# M_D_ext_power2.net
KiCad netlist of a schematic drawn in EAGLE
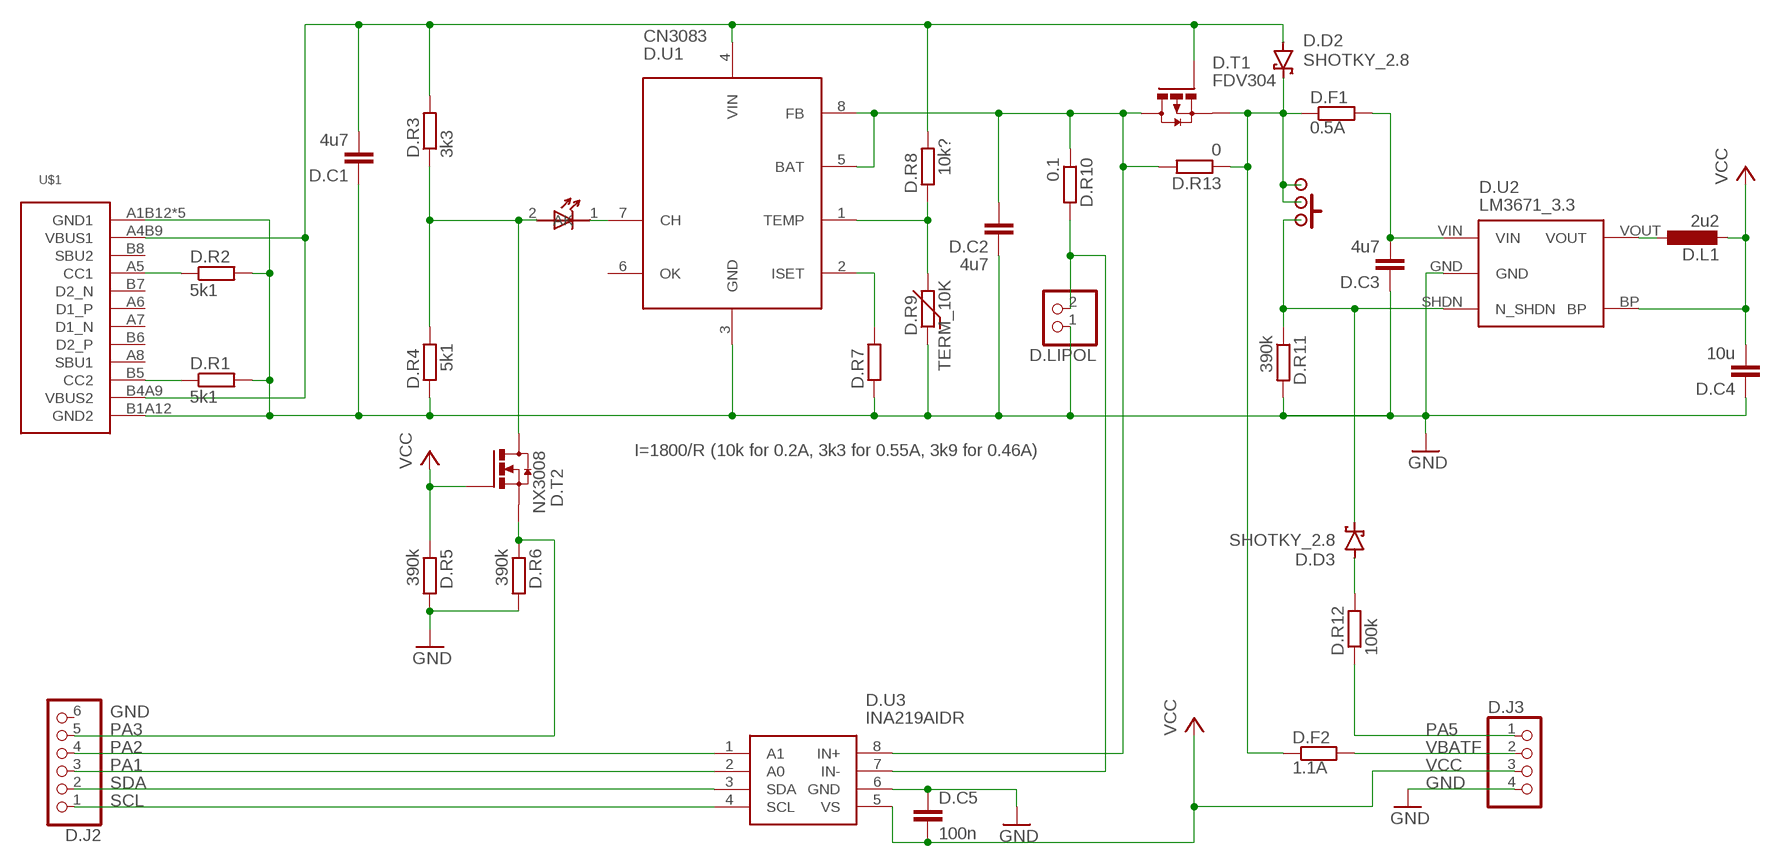
[diagram p0: schematic, sheet 1]

(export (version "E")
  (design (tool "Eeschema 10.0.6"))
  (components
    (comp (ref "D.C1")
      (value "4u7")
      (footprint "eagle-import:C0603")
      (libsource (lib "eagle-import") (part "C-EUC0603"))
    )
    (comp (ref "D.C2")
      (value "4u7")
      (footprint "eagle-import:C0603")
      (libsource (lib "eagle-import") (part "C-EUC0603"))
    )
    (comp (ref "D.C3")
      (value "4u7")
      (footprint "eagle-import:C0603")
      (libsource (lib "eagle-import") (part "C-EUC0603"))
    )
    (comp (ref "D.C4")
      (value "10u")
      (footprint "eagle-import:C0805")
      (libsource (lib "eagle-import") (part "C-EUC0805"))
    )
    (comp (ref "D.C5")
      (value "100n")
      (footprint "eagle-import:C0603")
      (libsource (lib "eagle-import") (part "C-EUC0603"))
    )
    (comp (ref "D.D1")
      (value "LED_1.8")
      (footprint "eagle-import:LED_1.8")
      (libsource (lib "eagle-import") (part "LED_1.8"))
    )
    (comp (ref "D.D2")
      (value "SHOTKY_2.8")
      (footprint "eagle-import:SHOTKY_2.8")
      (libsource (lib "eagle-import") (part "SHOTKY_2.8"))
    )
    (comp (ref "D.D3")
      (value "SHOTKY_2.8")
      (footprint "eagle-import:SHOTKY_2.8")
      (libsource (lib "eagle-import") (part "SHOTKY_2.8"))
    )
    (comp (ref "D.F1")
      (value "0.5A")
      (footprint "eagle-import:R0805")
      (libsource (lib "eagle-import") (part "R-EU_R0805"))
    )
    (comp (ref "D.F2")
      (value "1.1A")
      (footprint "eagle-import:R0805")
      (libsource (lib "eagle-import") (part "R-EU_R0805"))
    )
    (comp (ref "D.J2")
      (value "PINHD-1X6")
      (footprint "eagle-import:1X06")
      (libsource (lib "eagle-import") (part "PINHD-1X6"))
    )
    (comp (ref "D.J3")
      (value "PINHD-1X4")
      (footprint "eagle-import:1X04")
      (libsource (lib "eagle-import") (part "PINHD-1X4"))
    )
    (comp (ref "D.L1")
      (value "2u2")
      (footprint "eagle-import:L3230M")
      (libsource (lib "eagle-import") (part "L-EUL3230M"))
    )
    (comp (ref "D.LIPOL")
      (value "PINHD-1X21X2-2")
      (footprint "eagle-import:1X02-2")
      (libsource (lib "eagle-import") (part "PINHD-1X21X2-2"))
    )
    (comp (ref "D.ON/OFF/RESET")
      (value "SWITCH")
      (footprint "eagle-import:SWITCH")
      (libsource (lib "eagle-import") (part "SWITCH"))
    )
    (comp (ref "D.R1")
      (value "5k1")
      (footprint "eagle-import:R0603")
      (libsource (lib "eagle-import") (part "R-EU_R0603"))
    )
    (comp (ref "D.R2")
      (value "5k1")
      (footprint "eagle-import:R0603")
      (libsource (lib "eagle-import") (part "R-EU_R0603"))
    )
    (comp (ref "D.R3")
      (value "3k3")
      (footprint "eagle-import:R0603")
      (libsource (lib "eagle-import") (part "R-EU_R0603"))
    )
    (comp (ref "D.R4")
      (value "5k1")
      (footprint "eagle-import:R0603")
      (libsource (lib "eagle-import") (part "R-EU_R0603"))
    )
    (comp (ref "D.R5")
      (value "390k")
      (footprint "eagle-import:R0603")
      (libsource (lib "eagle-import") (part "R-EU_R0603"))
    )
    (comp (ref "D.R6")
      (value "390k")
      (footprint "eagle-import:R0603")
      (libsource (lib "eagle-import") (part "R-EU_R0603"))
    )
    (comp (ref "D.R7")
      (value "I=1800/R (10k for 0.2A, 3k3 for 0.55A, 3k9 for 0.46A)")
      (footprint "eagle-import:R0603")
      (libsource (lib "eagle-import") (part "R-EU_R0603"))
    )
    (comp (ref "D.R8")
      (value "10k?")
      (footprint "eagle-import:R0603")
      (libsource (lib "eagle-import") (part "R-EU_R0603"))
    )
    (comp (ref "D.R9")
      (value "TERM_10K")
      (footprint "eagle-import:THERM")
      (libsource (lib "eagle-import") (part "THERM"))
    )
    (comp (ref "D.R10")
      (value "0.1")
      (footprint "eagle-import:R0805")
      (libsource (lib "eagle-import") (part "R-EU_R0805"))
    )
    (comp (ref "D.R11")
      (value "390k")
      (footprint "eagle-import:R0603")
      (libsource (lib "eagle-import") (part "R-EU_R0603"))
    )
    (comp (ref "D.R12")
      (value "100k")
      (footprint "eagle-import:R0603")
      (libsource (lib "eagle-import") (part "R-EU_R0603"))
    )
    (comp (ref "D.R13")
      (value "0")
      (footprint "eagle-import:R0603")
      (libsource (lib "eagle-import") (part "R-EU_R0603"))
    )
    (comp (ref "D.T1")
      (value "FDV304")
      (footprint "eagle-import:SO23")
      (libsource (lib "eagle-import") (part "P-MOSFET"))
    )
    (comp (ref "D.T2")
      (value "NX3008")
      (footprint "eagle-import:SO23")
      (libsource (lib "eagle-import") (part "N-MOSFET"))
    )
    (comp (ref "D.U1")
      (value "CN3083")
      (footprint "eagle-import:SOP8")
      (libsource (lib "eagle-import") (part "CN3083"))
    )
    (comp (ref "D.U2")
      (value "LM3671_3.3")
      (footprint "eagle-import:SOT32-5")
      (libsource (lib "eagle-import") (part "STABILISER_APE8865"))
    )
    (comp (ref "D.U3")
      (value "INA219AIDR")
      (footprint "eagle-import:SOIC127P600X175-8N")
      (fields (field (name "MOUSER_PART_NUMBER") "595-INA219AIDR"))
      (libsource (lib "eagle-import") (part "INA219AIDR"))
    )
    (comp (ref "U$1")
      (value "USB-C")
      (footprint "eagle-import:USB-C")
      (libsource (lib "eagle-import") (part "USB-C"))
    )
  )
  (nets
    (net (code "1") (name "/PA1") (class "Default")
      (node (ref "D.J2") (pin "3") (pinfunction "3_3") (pintype "passive"))
      (node (ref "D.U3") (pin "2") (pinfunction "A0_2") (pintype "bidirectional"))
    )
    (net (code "2") (name "/PA2") (class "Default")
      (node (ref "D.J2") (pin "4") (pinfunction "4_4") (pintype "passive"))
      (node (ref "D.U3") (pin "1") (pinfunction "A1_1") (pintype "bidirectional"))
    )
    (net (code "3") (name "/PA3") (class "Default")
      (node (ref "D.J2") (pin "5") (pinfunction "5_5") (pintype "passive"))
      (node (ref "D.R6") (pin "1") (pinfunction "1_1") (pintype "passive"))
      (node (ref "D.T2") (pin "S") (pinfunction "S_S") (pintype "passive"))
    )
    (net (code "4") (name "/PA5") (class "Default")
      (node (ref "D.C1") (pin "2") (pinfunction "2_2") (pintype "passive"))
      (node (ref "D.D2") (pin "A") (pinfunction "A_A") (pintype "passive"))
      (node (ref "D.R3") (pin "2") (pinfunction "2_2") (pintype "passive"))
      (node (ref "D.R8") (pin "2") (pinfunction "2_2") (pintype "passive"))
      (node (ref "D.T1") (pin "G") (pinfunction "G_G") (pintype "passive"))
      (node (ref "D.U1") (pin "4") (pinfunction "VIN_4") (pintype "bidirectional"))
      (node (ref "U$1") (pin "A4B9") (pinfunction "VBUS1_A4B9") (pintype "bidirectional"))
      (node (ref "U$1") (pin "B4A9") (pinfunction "VBUS2_B4A9") (pintype "bidirectional"))
    )
    (net (code "5") (name "/SCL") (class "Default")
      (node (ref "D.J2") (pin "1") (pinfunction "1_1") (pintype "passive"))
      (node (ref "D.U3") (pin "4") (pinfunction "SCL_4") (pintype "bidirectional"))
    )
    (net (code "6") (name "/SDA") (class "Default")
      (node (ref "D.J2") (pin "2") (pinfunction "2_2") (pintype "passive"))
      (node (ref "D.U3") (pin "3") (pinfunction "SDA_3") (pintype "bidirectional"))
    )
    (net (code "7") (name "/VBATF") (class "Default")
      (node (ref "D.F2") (pin "2") (pinfunction "2_2") (pintype "passive"))
      (node (ref "D.J3") (pin "2") (pinfunction "2_2") (pintype "passive"))
    )
    (net (code "8") (name "GND") (class "Default")
      (node (ref "D.C1") (pin "1") (pinfunction "1_1") (pintype "passive"))
      (node (ref "D.C2") (pin "1") (pinfunction "1_1") (pintype "passive"))
      (node (ref "D.C3") (pin "1") (pinfunction "1_1") (pintype "passive"))
      (node (ref "D.C4") (pin "1") (pinfunction "1_1") (pintype "passive"))
      (node (ref "D.C5") (pin "1") (pinfunction "1_1") (pintype "passive"))
      (node (ref "D.J3") (pin "4") (pinfunction "4_4") (pintype "passive"))
      (node (ref "D.LIPOL") (pin "1") (pinfunction "1_1") (pintype "passive"))
      (node (ref "D.R1") (pin "2") (pinfunction "2_2") (pintype "passive"))
      (node (ref "D.R11") (pin "2") (pinfunction "2_2") (pintype "passive"))
      (node (ref "D.R2") (pin "2") (pinfunction "2_2") (pintype "passive"))
      (node (ref "D.R4") (pin "1") (pinfunction "1_1") (pintype "passive"))
      (node (ref "D.R5") (pin "2") (pinfunction "2_2") (pintype "passive"))
      (node (ref "D.R6") (pin "2") (pinfunction "2_2") (pintype "passive"))
      (node (ref "D.R7") (pin "1") (pinfunction "1_1") (pintype "passive"))
      (node (ref "D.R9") (pin "1") (pinfunction "1_1") (pintype "passive"))
      (node (ref "D.U1") (pin "3") (pinfunction "GND_3") (pintype "bidirectional"))
      (node (ref "D.U2") (pin "GND") (pinfunction "GND_GND") (pintype "bidirectional"))
      (node (ref "D.U3") (pin "6") (pinfunction "GND_6") (pintype "bidirectional"))
      (node (ref "U$1") (pin "A1B12") (pinfunction "GND1_A1B12") (pintype "bidirectional"))
      (node (ref "U$1") (pin "B1A12") (pinfunction "GND2_B1A12") (pintype "bidirectional"))
      (node (ref "U$1") (pin "SH1") (pinfunction "GND1_SH1") (pintype "bidirectional"))
      (node (ref "U$1") (pin "SH2") (pinfunction "GND1_SH2") (pintype "bidirectional"))
      (node (ref "U$1") (pin "SH3") (pinfunction "GND1_SH3") (pintype "bidirectional"))
      (node (ref "U$1") (pin "SH4") (pinfunction "GND1_SH4") (pintype "bidirectional"))
    )
    (net (code "9") (name "Net-(D.C3-Pad2)") (class "Default")
      (node (ref "D.C3") (pin "2") (pinfunction "2_2") (pintype "passive"))
      (node (ref "D.F1") (pin "2") (pinfunction "2_2") (pintype "passive"))
      (node (ref "D.U2") (pin "VIN") (pinfunction "VIN_VIN") (pintype "bidirectional"))
    )
    (net (code "10") (name "Net-(D.D1-A)") (class "Default")
      (node (ref "D.D1") (pin "2") (pinfunction "A_2") (pintype "bidirectional"))
      (node (ref "D.R3") (pin "1") (pinfunction "1_1") (pintype "passive"))
      (node (ref "D.R4") (pin "2") (pinfunction "2_2") (pintype "passive"))
      (node (ref "D.T2") (pin "D") (pinfunction "D_D") (pintype "passive"))
    )
    (net (code "11") (name "Net-(D.D1-K)") (class "Default")
      (node (ref "D.D1") (pin "1") (pinfunction "K_1") (pintype "bidirectional"))
      (node (ref "D.U1") (pin "7") (pinfunction "CH_7") (pintype "bidirectional"))
    )
    (net (code "12") (name "Net-(D.D2-C)") (class "Default")
      (node (ref "D.D2") (pin "K") (pinfunction "C_K") (pintype "passive"))
      (node (ref "D.F1") (pin "1") (pinfunction "1_1") (pintype "passive"))
      (node (ref "D.F2") (pin "1") (pinfunction "1_1") (pintype "passive"))
      (node (ref "D.ON/OFF/RESET") (pin "P$2") (pinfunction "P$2_P$2") (pintype "bidirectional"))
      (node (ref "D.ON/OFF/RESET") (pin "P$3") (pinfunction "P$3_P$3") (pintype "bidirectional"))
      (node (ref "D.ON/OFF/RESET") (pin "P$4") (pinfunction "P$3_P$4") (pintype "bidirectional"))
      (node (ref "D.ON/OFF/RESET") (pin "P$6") (pinfunction "P$3_P$6") (pintype "bidirectional"))
      (node (ref "D.R13") (pin "1") (pinfunction "1_1") (pintype "passive"))
      (node (ref "D.T1") (pin "S") (pinfunction "S_S") (pintype "passive"))
    )
    (net (code "13") (name "Net-(D.D3-C)") (class "Default")
      (node (ref "D.D3") (pin "K") (pinfunction "C_K") (pintype "passive"))
      (node (ref "D.ON/OFF/RESET") (pin "P$1") (pinfunction "P$1_P$1") (pintype "bidirectional"))
      (node (ref "D.ON/OFF/RESET") (pin "P$5") (pinfunction "P$1_P$5") (pintype "bidirectional"))
      (node (ref "D.ON/OFF/RESET") (pin "P$7") (pinfunction "P$1_P$7") (pintype "bidirectional"))
      (node (ref "D.R11") (pin "1") (pinfunction "1_1") (pintype "passive"))
      (node (ref "D.U2") (pin "SHDN") (pinfunction "N_SHDN_SHDN") (pintype "bidirectional"))
    )
    (net (code "14") (name "Net-(D.D3-PadA)") (class "Default")
      (node (ref "D.D3") (pin "A") (pinfunction "A_A") (pintype "passive"))
      (node (ref "D.R12") (pin "2") (pinfunction "2_2") (pintype "passive"))
    )
    (net (code "15") (name "Net-(D.J3-Pad1)") (class "Default")
      (node (ref "D.J3") (pin "1") (pinfunction "1_1") (pintype "passive"))
      (node (ref "D.R12") (pin "1") (pinfunction "1_1") (pintype "passive"))
    )
    (net (code "16") (name "Net-(D.L1-Pad1)") (class "Default")
      (node (ref "D.L1") (pin "1") (pinfunction "1_1") (pintype "passive"))
      (node (ref "D.U2") (pin "VOUT") (pinfunction "VOUT_VOUT") (pintype "bidirectional"))
    )
    (net (code "17") (name "Net-(D.U1-BAT)") (class "Default")
      (node (ref "D.C2") (pin "2") (pinfunction "2_2") (pintype "passive"))
      (node (ref "D.R10") (pin "1") (pinfunction "1_1") (pintype "passive"))
      (node (ref "D.R13") (pin "2") (pinfunction "2_2") (pintype "passive"))
      (node (ref "D.T1") (pin "D") (pinfunction "D_D") (pintype "passive"))
      (node (ref "D.U1") (pin "5") (pinfunction "BAT_5") (pintype "bidirectional"))
      (node (ref "D.U1") (pin "8") (pinfunction "FB_8") (pintype "bidirectional"))
      (node (ref "D.U3") (pin "8") (pinfunction "IN+_8") (pintype "bidirectional"))
    )
    (net (code "18") (name "Net-(D.U1-ISET)") (class "Default")
      (node (ref "D.R7") (pin "2") (pinfunction "2_2") (pintype "passive"))
      (node (ref "D.U1") (pin "2") (pinfunction "ISET_2") (pintype "bidirectional"))
    )
    (net (code "19") (name "Net-(D.U1-TEMP)") (class "Default")
      (node (ref "D.R8") (pin "1") (pinfunction "1_1") (pintype "passive"))
      (node (ref "D.R9") (pin "2") (pinfunction "2_2") (pintype "passive"))
      (node (ref "D.U1") (pin "1") (pinfunction "TEMP_1") (pintype "bidirectional"))
    )
    (net (code "20") (name "Net-(D.U3-IN-)") (class "Default")
      (node (ref "D.LIPOL") (pin "2") (pinfunction "2_2") (pintype "passive"))
      (node (ref "D.R10") (pin "2") (pinfunction "2_2") (pintype "passive"))
      (node (ref "D.U3") (pin "7") (pinfunction "IN-_7") (pintype "bidirectional"))
    )
    (net (code "21") (name "Net-(U$1-CC1)") (class "Default")
      (node (ref "D.R2") (pin "1") (pinfunction "1_1") (pintype "passive"))
      (node (ref "U$1") (pin "A5") (pinfunction "CC1_A5") (pintype "bidirectional"))
    )
    (net (code "22") (name "Net-(U$1-CC2)") (class "Default")
      (node (ref "D.R1") (pin "1") (pinfunction "1_1") (pintype "passive"))
      (node (ref "U$1") (pin "B5") (pinfunction "CC2_B5") (pintype "bidirectional"))
    )
    (net (code "23") (name "VCC") (class "Default")
      (node (ref "D.C4") (pin "2") (pinfunction "2_2") (pintype "passive"))
      (node (ref "D.C5") (pin "2") (pinfunction "2_2") (pintype "passive"))
      (node (ref "D.J3") (pin "3") (pinfunction "3_3") (pintype "passive"))
      (node (ref "D.L1") (pin "2") (pinfunction "2_2") (pintype "passive"))
      (node (ref "D.R5") (pin "1") (pinfunction "1_1") (pintype "passive"))
      (node (ref "D.T2") (pin "G") (pinfunction "G_G") (pintype "passive"))
      (node (ref "D.U2") (pin "BP") (pinfunction "BP_BP") (pintype "bidirectional"))
      (node (ref "D.U3") (pin "5") (pinfunction "VS_5") (pintype "bidirectional"))
    )
    (net (code "24") (name "unconnected-(D.J2-Pad6)") (class "Default")
      (node (ref "D.J2") (pin "6") (pinfunction "6_6") (pintype "passive"))
    )
    (net (code "25") (name "unconnected-(D.U1-OK-Pad6)") (class "Default")
      (node (ref "D.U1") (pin "6") (pinfunction "OK_6") (pintype "bidirectional"))
    )
    (net (code "26") (name "unconnected-(U$1-D1_N-PadA7)") (class "Default")
      (node (ref "U$1") (pin "A7") (pinfunction "D1_N_A7") (pintype "bidirectional"))
    )
    (net (code "27") (name "unconnected-(U$1-D1_P-PadA6)") (class "Default")
      (node (ref "U$1") (pin "A6") (pinfunction "D1_P_A6") (pintype "bidirectional"))
    )
    (net (code "28") (name "unconnected-(U$1-D2_N-PadB7)") (class "Default")
      (node (ref "U$1") (pin "B7") (pinfunction "D2_N_B7") (pintype "bidirectional"))
    )
    (net (code "29") (name "unconnected-(U$1-D2_P-PadB6)") (class "Default")
      (node (ref "U$1") (pin "B6") (pinfunction "D2_P_B6") (pintype "bidirectional"))
    )
    (net (code "30") (name "unconnected-(U$1-SBU1-PadA8)") (class "Default")
      (node (ref "U$1") (pin "A8") (pinfunction "SBU1_A8") (pintype "bidirectional"))
    )
    (net (code "31") (name "unconnected-(U$1-SBU2-PadB8)") (class "Default")
      (node (ref "U$1") (pin "B8") (pinfunction "SBU2_B8") (pintype "bidirectional"))
    )
  )
)
